# BridgeBoard.net
KiCad netlist of a schematic drawn in Altium Designer
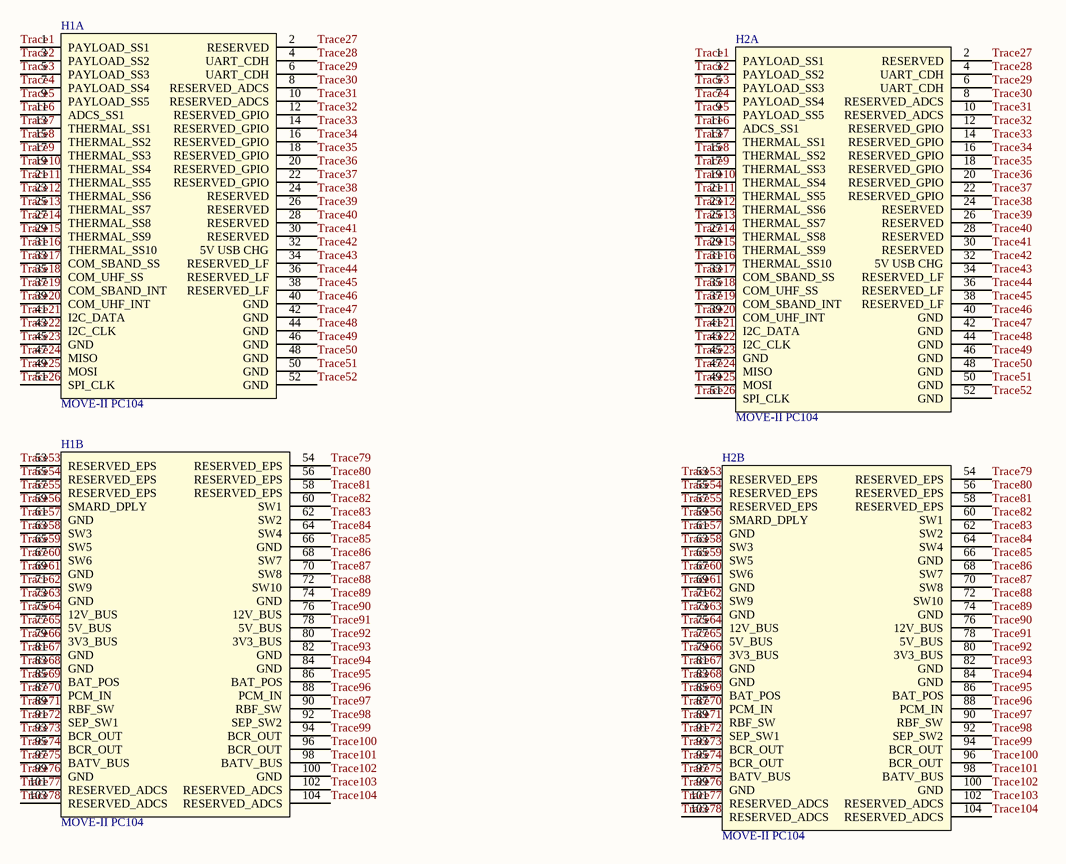
[diagram p0: BridgeBoard.SchDoc]

(export (version "E")
  (design (tool "Eeschema 10.0.6"))
  (components
    (comp (ref "H1")
      (value "MOVE-II PC104")
      (footprint "PC104")
      (libsource (lib "PC104_singleHeader") (part "MOVE-II PC104"))
    )
    (comp (ref "H2")
      (value "MOVE-II PC104")
      (footprint "PC104")
      (libsource (lib "PC104_singleHeader") (part "MOVE-II PC104"))
    )
  )
  (nets
    (net (code "1") (name "/Trace1") (class "Default")
      (node (ref "H1") (pin "1") (pinfunction "PAYLOAD_SS1_1") (pintype "passive"))
      (node (ref "H2") (pin "1") (pinfunction "PAYLOAD_SS1_1") (pintype "passive"))
    )
    (net (code "2") (name "/Trace2") (class "Default")
      (node (ref "H1") (pin "3") (pinfunction "PAYLOAD_SS2_3") (pintype "passive"))
      (node (ref "H2") (pin "3") (pinfunction "PAYLOAD_SS2_3") (pintype "passive"))
    )
    (net (code "3") (name "/Trace3") (class "Default")
      (node (ref "H1") (pin "5") (pinfunction "PAYLOAD_SS3_5") (pintype "passive"))
      (node (ref "H2") (pin "5") (pinfunction "PAYLOAD_SS3_5") (pintype "passive"))
    )
    (net (code "4") (name "/Trace4") (class "Default")
      (node (ref "H1") (pin "7") (pinfunction "PAYLOAD_SS4_7") (pintype "passive"))
      (node (ref "H2") (pin "7") (pinfunction "PAYLOAD_SS4_7") (pintype "passive"))
    )
    (net (code "5") (name "/Trace5") (class "Default")
      (node (ref "H1") (pin "9") (pinfunction "PAYLOAD_SS5_9") (pintype "passive"))
      (node (ref "H2") (pin "9") (pinfunction "PAYLOAD_SS5_9") (pintype "passive"))
    )
    (net (code "6") (name "/Trace6") (class "Default")
      (node (ref "H1") (pin "11") (pinfunction "ADCS_SS1_11") (pintype "passive"))
      (node (ref "H2") (pin "11") (pinfunction "ADCS_SS1_11") (pintype "passive"))
    )
    (net (code "7") (name "/Trace7") (class "Default")
      (node (ref "H1") (pin "13") (pinfunction "THERMAL_SS1_13") (pintype "passive"))
      (node (ref "H2") (pin "13") (pinfunction "THERMAL_SS1_13") (pintype "passive"))
    )
    (net (code "8") (name "/Trace8") (class "Default")
      (node (ref "H1") (pin "15") (pinfunction "THERMAL_SS2_15") (pintype "passive"))
      (node (ref "H2") (pin "15") (pinfunction "THERMAL_SS2_15") (pintype "passive"))
    )
    (net (code "9") (name "/Trace9") (class "Default")
      (node (ref "H1") (pin "17") (pinfunction "THERMAL_SS3_17") (pintype "passive"))
      (node (ref "H2") (pin "17") (pinfunction "THERMAL_SS3_17") (pintype "passive"))
    )
    (net (code "10") (name "/Trace10") (class "Default")
      (node (ref "H1") (pin "19") (pinfunction "THERMAL_SS4_19") (pintype "passive"))
      (node (ref "H2") (pin "19") (pinfunction "THERMAL_SS4_19") (pintype "passive"))
    )
    (net (code "11") (name "/Trace11") (class "Default")
      (node (ref "H1") (pin "21") (pinfunction "THERMAL_SS5_21") (pintype "passive"))
      (node (ref "H2") (pin "21") (pinfunction "THERMAL_SS5_21") (pintype "passive"))
    )
    (net (code "12") (name "/Trace12") (class "Default")
      (node (ref "H1") (pin "23") (pinfunction "THERMAL_SS6_23") (pintype "passive"))
      (node (ref "H2") (pin "23") (pinfunction "THERMAL_SS6_23") (pintype "passive"))
    )
    (net (code "13") (name "/Trace13") (class "Default")
      (node (ref "H1") (pin "25") (pinfunction "THERMAL_SS7_25") (pintype "passive"))
      (node (ref "H2") (pin "25") (pinfunction "THERMAL_SS7_25") (pintype "passive"))
    )
    (net (code "14") (name "/Trace14") (class "Default")
      (node (ref "H1") (pin "27") (pinfunction "THERMAL_SS8_27") (pintype "passive"))
      (node (ref "H2") (pin "27") (pinfunction "THERMAL_SS8_27") (pintype "passive"))
    )
    (net (code "15") (name "/Trace15") (class "Default")
      (node (ref "H1") (pin "29") (pinfunction "THERMAL_SS9_29") (pintype "passive"))
      (node (ref "H2") (pin "29") (pinfunction "THERMAL_SS9_29") (pintype "passive"))
    )
    (net (code "16") (name "/Trace16") (class "Default")
      (node (ref "H1") (pin "31") (pinfunction "THERMAL_SS10_31") (pintype "passive"))
      (node (ref "H2") (pin "31") (pinfunction "THERMAL_SS10_31") (pintype "passive"))
    )
    (net (code "17") (name "/Trace17") (class "Default")
      (node (ref "H1") (pin "33") (pinfunction "COM_SBAND_SS_33") (pintype "passive"))
      (node (ref "H2") (pin "33") (pinfunction "COM_SBAND_SS_33") (pintype "passive"))
    )
    (net (code "18") (name "/Trace18") (class "Default")
      (node (ref "H1") (pin "35") (pinfunction "COM_UHF_SS_35") (pintype "passive"))
      (node (ref "H2") (pin "35") (pinfunction "COM_UHF_SS_35") (pintype "passive"))
    )
    (net (code "19") (name "/Trace19") (class "Default")
      (node (ref "H1") (pin "37") (pinfunction "COM_SBAND_INT_37") (pintype "passive"))
      (node (ref "H2") (pin "37") (pinfunction "COM_SBAND_INT_37") (pintype "passive"))
    )
    (net (code "20") (name "/Trace20") (class "Default")
      (node (ref "H1") (pin "39") (pinfunction "COM_UHF_INT_39") (pintype "passive"))
      (node (ref "H2") (pin "39") (pinfunction "COM_UHF_INT_39") (pintype "passive"))
    )
    (net (code "21") (name "/Trace21") (class "Default")
      (node (ref "H1") (pin "41") (pinfunction "I2C_DATA_41") (pintype "passive"))
      (node (ref "H2") (pin "41") (pinfunction "I2C_DATA_41") (pintype "passive"))
    )
    (net (code "22") (name "/Trace22") (class "Default")
      (node (ref "H1") (pin "43") (pinfunction "I2C_CLK_43") (pintype "passive"))
      (node (ref "H2") (pin "43") (pinfunction "I2C_CLK_43") (pintype "passive"))
    )
    (net (code "23") (name "/Trace23") (class "Default")
      (node (ref "H1") (pin "45") (pinfunction "GND_45") (pintype "passive"))
      (node (ref "H2") (pin "45") (pinfunction "GND_45") (pintype "passive"))
    )
    (net (code "24") (name "/Trace24") (class "Default")
      (node (ref "H1") (pin "47") (pinfunction "MISO_47") (pintype "passive"))
      (node (ref "H2") (pin "47") (pinfunction "MISO_47") (pintype "passive"))
    )
    (net (code "25") (name "/Trace25") (class "Default")
      (node (ref "H1") (pin "49") (pinfunction "MOSI_49") (pintype "passive"))
      (node (ref "H2") (pin "49") (pinfunction "MOSI_49") (pintype "passive"))
    )
    (net (code "26") (name "/Trace26") (class "Default")
      (node (ref "H1") (pin "51") (pinfunction "SPI_CLK_51") (pintype "passive"))
      (node (ref "H2") (pin "51") (pinfunction "SPI_CLK_51") (pintype "passive"))
    )
    (net (code "27") (name "/Trace27") (class "Default")
      (node (ref "H1") (pin "2") (pinfunction "RESERVED_2") (pintype "passive"))
      (node (ref "H2") (pin "2") (pinfunction "RESERVED_2") (pintype "passive"))
    )
    (net (code "28") (name "/Trace28") (class "Default")
      (node (ref "H1") (pin "4") (pinfunction "UART_CDH_4") (pintype "passive"))
      (node (ref "H2") (pin "4") (pinfunction "UART_CDH_4") (pintype "passive"))
    )
    (net (code "29") (name "/Trace29") (class "Default")
      (node (ref "H1") (pin "6") (pinfunction "UART_CDH_6") (pintype "passive"))
      (node (ref "H2") (pin "6") (pinfunction "UART_CDH_6") (pintype "passive"))
    )
    (net (code "30") (name "/Trace30") (class "Default")
      (node (ref "H1") (pin "8") (pinfunction "RESERVED_ADCS_8") (pintype "passive"))
      (node (ref "H2") (pin "8") (pinfunction "RESERVED_ADCS_8") (pintype "passive"))
    )
    (net (code "31") (name "/Trace31") (class "Default")
      (node (ref "H1") (pin "10") (pinfunction "RESERVED_ADCS_10") (pintype "passive"))
      (node (ref "H2") (pin "10") (pinfunction "RESERVED_ADCS_10") (pintype "passive"))
    )
    (net (code "32") (name "/Trace32") (class "Default")
      (node (ref "H1") (pin "12") (pinfunction "RESERVED_GPIO_12") (pintype "passive"))
      (node (ref "H2") (pin "12") (pinfunction "RESERVED_GPIO_12") (pintype "passive"))
    )
    (net (code "33") (name "/Trace33") (class "Default")
      (node (ref "H1") (pin "14") (pinfunction "RESERVED_GPIO_14") (pintype "passive"))
      (node (ref "H2") (pin "14") (pinfunction "RESERVED_GPIO_14") (pintype "passive"))
    )
    (net (code "34") (name "/Trace34") (class "Default")
      (node (ref "H1") (pin "16") (pinfunction "RESERVED_GPIO_16") (pintype "passive"))
      (node (ref "H2") (pin "16") (pinfunction "RESERVED_GPIO_16") (pintype "passive"))
    )
    (net (code "35") (name "/Trace35") (class "Default")
      (node (ref "H1") (pin "18") (pinfunction "RESERVED_GPIO_18") (pintype "passive"))
      (node (ref "H2") (pin "18") (pinfunction "RESERVED_GPIO_18") (pintype "passive"))
    )
    (net (code "36") (name "/Trace36") (class "Default")
      (node (ref "H1") (pin "20") (pinfunction "RESERVED_GPIO_20") (pintype "passive"))
      (node (ref "H2") (pin "20") (pinfunction "RESERVED_GPIO_20") (pintype "passive"))
    )
    (net (code "37") (name "/Trace37") (class "Default")
      (node (ref "H1") (pin "22") (pinfunction "RESERVED_GPIO_22") (pintype "passive"))
      (node (ref "H2") (pin "22") (pinfunction "RESERVED_GPIO_22") (pintype "passive"))
    )
    (net (code "38") (name "/Trace38") (class "Default")
      (node (ref "H1") (pin "24") (pinfunction "RESERVED_24") (pintype "passive"))
      (node (ref "H2") (pin "24") (pinfunction "RESERVED_24") (pintype "passive"))
    )
    (net (code "39") (name "/Trace39") (class "Default")
      (node (ref "H1") (pin "26") (pinfunction "RESERVED_26") (pintype "passive"))
      (node (ref "H2") (pin "26") (pinfunction "RESERVED_26") (pintype "passive"))
    )
    (net (code "40") (name "/Trace40") (class "Default")
      (node (ref "H1") (pin "28") (pinfunction "RESERVED_28") (pintype "passive"))
      (node (ref "H2") (pin "28") (pinfunction "RESERVED_28") (pintype "passive"))
    )
    (net (code "41") (name "/Trace41") (class "Default")
      (node (ref "H1") (pin "30") (pinfunction "RESERVED_30") (pintype "passive"))
      (node (ref "H2") (pin "30") (pinfunction "RESERVED_30") (pintype "passive"))
    )
    (net (code "42") (name "/Trace42") (class "Default")
      (node (ref "H1") (pin "32") (pinfunction "5V_USB_CHG_32") (pintype "passive"))
      (node (ref "H2") (pin "32") (pinfunction "5V_USB_CHG_32") (pintype "passive"))
    )
    (net (code "43") (name "/Trace43") (class "Default")
      (node (ref "H1") (pin "34") (pinfunction "RESERVED_LF_34") (pintype "passive"))
      (node (ref "H2") (pin "34") (pinfunction "RESERVED_LF_34") (pintype "passive"))
    )
    (net (code "44") (name "/Trace44") (class "Default")
      (node (ref "H1") (pin "36") (pinfunction "RESERVED_LF_36") (pintype "passive"))
      (node (ref "H2") (pin "36") (pinfunction "RESERVED_LF_36") (pintype "passive"))
    )
    (net (code "45") (name "/Trace45") (class "Default")
      (node (ref "H1") (pin "38") (pinfunction "RESERVED_LF_38") (pintype "passive"))
      (node (ref "H2") (pin "38") (pinfunction "RESERVED_LF_38") (pintype "passive"))
    )
    (net (code "46") (name "/Trace46") (class "Default")
      (node (ref "H1") (pin "40") (pinfunction "GND_40") (pintype "passive"))
      (node (ref "H2") (pin "40") (pinfunction "GND_40") (pintype "passive"))
    )
    (net (code "47") (name "/Trace47") (class "Default")
      (node (ref "H1") (pin "42") (pinfunction "GND_42") (pintype "passive"))
      (node (ref "H2") (pin "42") (pinfunction "GND_42") (pintype "passive"))
    )
    (net (code "48") (name "/Trace48") (class "Default")
      (node (ref "H1") (pin "44") (pinfunction "GND_44") (pintype "passive"))
      (node (ref "H2") (pin "44") (pinfunction "GND_44") (pintype "passive"))
    )
    (net (code "49") (name "/Trace49") (class "Default")
      (node (ref "H1") (pin "46") (pinfunction "GND_46") (pintype "passive"))
      (node (ref "H2") (pin "46") (pinfunction "GND_46") (pintype "passive"))
    )
    (net (code "50") (name "/Trace50") (class "Default")
      (node (ref "H1") (pin "48") (pinfunction "GND_48") (pintype "passive"))
      (node (ref "H2") (pin "48") (pinfunction "GND_48") (pintype "passive"))
    )
    (net (code "51") (name "/Trace51") (class "Default")
      (node (ref "H1") (pin "50") (pinfunction "GND_50") (pintype "passive"))
      (node (ref "H2") (pin "50") (pinfunction "GND_50") (pintype "passive"))
    )
    (net (code "52") (name "/Trace52") (class "Default")
      (node (ref "H1") (pin "52") (pinfunction "GND_52") (pintype "passive"))
      (node (ref "H2") (pin "52") (pinfunction "GND_52") (pintype "passive"))
    )
    (net (code "53") (name "/Trace53") (class "Default")
      (node (ref "H1") (pin "53") (pinfunction "RESERVED_EPS_53") (pintype "passive"))
      (node (ref "H2") (pin "53") (pinfunction "RESERVED_EPS_53") (pintype "passive"))
    )
    (net (code "54") (name "/Trace54") (class "Default")
      (node (ref "H1") (pin "55") (pinfunction "RESERVED_EPS_55") (pintype "passive"))
      (node (ref "H2") (pin "55") (pinfunction "RESERVED_EPS_55") (pintype "passive"))
    )
    (net (code "55") (name "/Trace55") (class "Default")
      (node (ref "H1") (pin "57") (pinfunction "RESERVED_EPS_57") (pintype "passive"))
      (node (ref "H2") (pin "57") (pinfunction "RESERVED_EPS_57") (pintype "passive"))
    )
    (net (code "56") (name "/Trace56") (class "Default")
      (node (ref "H1") (pin "59") (pinfunction "SMARD_DPLY_59") (pintype "passive"))
      (node (ref "H2") (pin "59") (pinfunction "SMARD_DPLY_59") (pintype "passive"))
    )
    (net (code "57") (name "/Trace57") (class "Default")
      (node (ref "H1") (pin "61") (pinfunction "GND_61") (pintype "passive"))
      (node (ref "H2") (pin "61") (pinfunction "GND_61") (pintype "passive"))
    )
    (net (code "58") (name "/Trace58") (class "Default")
      (node (ref "H1") (pin "63") (pinfunction "SW3_63") (pintype "passive"))
      (node (ref "H2") (pin "63") (pinfunction "SW3_63") (pintype "passive"))
    )
    (net (code "59") (name "/Trace59") (class "Default")
      (node (ref "H1") (pin "65") (pinfunction "SW5_65") (pintype "passive"))
      (node (ref "H2") (pin "65") (pinfunction "SW5_65") (pintype "passive"))
    )
    (net (code "60") (name "/Trace60") (class "Default")
      (node (ref "H1") (pin "67") (pinfunction "SW6_67") (pintype "passive"))
      (node (ref "H2") (pin "67") (pinfunction "SW6_67") (pintype "passive"))
    )
    (net (code "61") (name "/Trace61") (class "Default")
      (node (ref "H1") (pin "69") (pinfunction "GND_69") (pintype "passive"))
      (node (ref "H2") (pin "69") (pinfunction "GND_69") (pintype "passive"))
    )
    (net (code "62") (name "/Trace62") (class "Default")
      (node (ref "H1") (pin "71") (pinfunction "SW9_71") (pintype "passive"))
      (node (ref "H2") (pin "71") (pinfunction "SW9_71") (pintype "passive"))
    )
    (net (code "63") (name "/Trace63") (class "Default")
      (node (ref "H1") (pin "73") (pinfunction "GND_73") (pintype "passive"))
      (node (ref "H2") (pin "73") (pinfunction "GND_73") (pintype "passive"))
    )
    (net (code "64") (name "/Trace64") (class "Default")
      (node (ref "H1") (pin "75") (pinfunction "12V_BUS_75") (pintype "passive"))
      (node (ref "H2") (pin "75") (pinfunction "12V_BUS_75") (pintype "passive"))
    )
    (net (code "65") (name "/Trace65") (class "Default")
      (node (ref "H1") (pin "77") (pinfunction "5V_BUS_77") (pintype "passive"))
      (node (ref "H2") (pin "77") (pinfunction "5V_BUS_77") (pintype "passive"))
    )
    (net (code "66") (name "/Trace66") (class "Default")
      (node (ref "H1") (pin "79") (pinfunction "3V3_BUS_79") (pintype "passive"))
      (node (ref "H2") (pin "79") (pinfunction "3V3_BUS_79") (pintype "passive"))
    )
    (net (code "67") (name "/Trace67") (class "Default")
      (node (ref "H1") (pin "81") (pinfunction "GND_81") (pintype "passive"))
      (node (ref "H2") (pin "81") (pinfunction "GND_81") (pintype "passive"))
    )
    (net (code "68") (name "/Trace68") (class "Default")
      (node (ref "H1") (pin "83") (pinfunction "GND_83") (pintype "passive"))
      (node (ref "H2") (pin "83") (pinfunction "GND_83") (pintype "passive"))
    )
    (net (code "69") (name "/Trace69") (class "Default")
      (node (ref "H1") (pin "85") (pinfunction "BAT_POS_85") (pintype "passive"))
      (node (ref "H2") (pin "85") (pinfunction "BAT_POS_85") (pintype "passive"))
    )
    (net (code "70") (name "/Trace70") (class "Default")
      (node (ref "H1") (pin "87") (pinfunction "PCM_IN_87") (pintype "passive"))
      (node (ref "H2") (pin "87") (pinfunction "PCM_IN_87") (pintype "passive"))
    )
    (net (code "71") (name "/Trace71") (class "Default")
      (node (ref "H1") (pin "89") (pinfunction "RBF_SW_89") (pintype "passive"))
      (node (ref "H2") (pin "89") (pinfunction "RBF_SW_89") (pintype "passive"))
    )
    (net (code "72") (name "/Trace72") (class "Default")
      (node (ref "H1") (pin "91") (pinfunction "SEP_SW1_91") (pintype "passive"))
      (node (ref "H2") (pin "91") (pinfunction "SEP_SW1_91") (pintype "passive"))
    )
    (net (code "73") (name "/Trace73") (class "Default")
      (node (ref "H1") (pin "93") (pinfunction "BCR_OUT_93") (pintype "passive"))
      (node (ref "H2") (pin "93") (pinfunction "BCR_OUT_93") (pintype "passive"))
    )
    (net (code "74") (name "/Trace74") (class "Default")
      (node (ref "H1") (pin "95") (pinfunction "BCR_OUT_95") (pintype "passive"))
      (node (ref "H2") (pin "95") (pinfunction "BCR_OUT_95") (pintype "passive"))
    )
    (net (code "75") (name "/Trace75") (class "Default")
      (node (ref "H1") (pin "97") (pinfunction "BATV_BUS_97") (pintype "passive"))
      (node (ref "H2") (pin "97") (pinfunction "BATV_BUS_97") (pintype "passive"))
    )
    (net (code "76") (name "/Trace76") (class "Default")
      (node (ref "H1") (pin "99") (pinfunction "GND_99") (pintype "passive"))
      (node (ref "H2") (pin "99") (pinfunction "GND_99") (pintype "passive"))
    )
    (net (code "77") (name "/Trace77") (class "Default")
      (node (ref "H1") (pin "101") (pinfunction "RESERVED_ADCS_101") (pintype "passive"))
      (node (ref "H2") (pin "101") (pinfunction "RESERVED_ADCS_101") (pintype "passive"))
    )
    (net (code "78") (name "/Trace78") (class "Default")
      (node (ref "H1") (pin "103") (pinfunction "RESERVED_ADCS_103") (pintype "passive"))
      (node (ref "H2") (pin "103") (pinfunction "RESERVED_ADCS_103") (pintype "passive"))
    )
    (net (code "79") (name "/Trace79") (class "Default")
      (node (ref "H1") (pin "54") (pinfunction "RESERVED_EPS_54") (pintype "passive"))
      (node (ref "H2") (pin "54") (pinfunction "RESERVED_EPS_54") (pintype "passive"))
    )
    (net (code "80") (name "/Trace80") (class "Default")
      (node (ref "H1") (pin "56") (pinfunction "RESERVED_EPS_56") (pintype "passive"))
      (node (ref "H2") (pin "56") (pinfunction "RESERVED_EPS_56") (pintype "passive"))
    )
    (net (code "81") (name "/Trace81") (class "Default")
      (node (ref "H1") (pin "58") (pinfunction "RESERVED_EPS_58") (pintype "passive"))
      (node (ref "H2") (pin "58") (pinfunction "RESERVED_EPS_58") (pintype "passive"))
    )
    (net (code "82") (name "/Trace82") (class "Default")
      (node (ref "H1") (pin "60") (pinfunction "SW1_60") (pintype "passive"))
      (node (ref "H2") (pin "60") (pinfunction "SW1_60") (pintype "passive"))
    )
    (net (code "83") (name "/Trace83") (class "Default")
      (node (ref "H1") (pin "62") (pinfunction "SW2_62") (pintype "passive"))
      (node (ref "H2") (pin "62") (pinfunction "SW2_62") (pintype "passive"))
    )
    (net (code "84") (name "/Trace84") (class "Default")
      (node (ref "H1") (pin "64") (pinfunction "SW4_64") (pintype "passive"))
      (node (ref "H2") (pin "64") (pinfunction "SW4_64") (pintype "passive"))
    )
    (net (code "85") (name "/Trace85") (class "Default")
      (node (ref "H1") (pin "66") (pinfunction "GND_66") (pintype "passive"))
      (node (ref "H2") (pin "66") (pinfunction "GND_66") (pintype "passive"))
    )
    (net (code "86") (name "/Trace86") (class "Default")
      (node (ref "H1") (pin "68") (pinfunction "SW7_68") (pintype "passive"))
      (node (ref "H2") (pin "68") (pinfunction "SW7_68") (pintype "passive"))
    )
    (net (code "87") (name "/Trace87") (class "Default")
      (node (ref "H1") (pin "70") (pinfunction "SW8_70") (pintype "passive"))
      (node (ref "H2") (pin "70") (pinfunction "SW8_70") (pintype "passive"))
    )
    (net (code "88") (name "/Trace88") (class "Default")
      (node (ref "H1") (pin "72") (pinfunction "SW10_72") (pintype "passive"))
      (node (ref "H2") (pin "72") (pinfunction "SW10_72") (pintype "passive"))
    )
    (net (code "89") (name "/Trace89") (class "Default")
      (node (ref "H1") (pin "74") (pinfunction "GND_74") (pintype "passive"))
      (node (ref "H2") (pin "74") (pinfunction "GND_74") (pintype "passive"))
    )
    (net (code "90") (name "/Trace90") (class "Default")
      (node (ref "H1") (pin "76") (pinfunction "12V_BUS_76") (pintype "passive"))
      (node (ref "H2") (pin "76") (pinfunction "12V_BUS_76") (pintype "passive"))
    )
    (net (code "91") (name "/Trace91") (class "Default")
      (node (ref "H1") (pin "78") (pinfunction "5V_BUS_78") (pintype "passive"))
      (node (ref "H2") (pin "78") (pinfunction "5V_BUS_78") (pintype "passive"))
    )
    (net (code "92") (name "/Trace92") (class "Default")
      (node (ref "H1") (pin "80") (pinfunction "3V3_BUS_80") (pintype "passive"))
      (node (ref "H2") (pin "80") (pinfunction "3V3_BUS_80") (pintype "passive"))
    )
    (net (code "93") (name "/Trace93") (class "Default")
      (node (ref "H1") (pin "82") (pinfunction "GND_82") (pintype "passive"))
      (node (ref "H2") (pin "82") (pinfunction "GND_82") (pintype "passive"))
    )
    (net (code "94") (name "/Trace94") (class "Default")
      (node (ref "H1") (pin "84") (pinfunction "GND_84") (pintype "passive"))
      (node (ref "H2") (pin "84") (pinfunction "GND_84") (pintype "passive"))
    )
    (net (code "95") (name "/Trace95") (class "Default")
      (node (ref "H1") (pin "86") (pinfunction "BAT_POS_86") (pintype "passive"))
      (node (ref "H2") (pin "86") (pinfunction "BAT_POS_86") (pintype "passive"))
    )
    (net (code "96") (name "/Trace96") (class "Default")
      (node (ref "H1") (pin "88") (pinfunction "PCM_IN_88") (pintype "passive"))
      (node (ref "H2") (pin "88") (pinfunction "PCM_IN_88") (pintype "passive"))
    )
    (net (code "97") (name "/Trace97") (class "Default")
      (node (ref "H1") (pin "90") (pinfunction "RBF_SW_90") (pintype "passive"))
      (node (ref "H2") (pin "90") (pinfunction "RBF_SW_90") (pintype "passive"))
    )
    (net (code "98") (name "/Trace98") (class "Default")
      (node (ref "H1") (pin "92") (pinfunction "SEP_SW2_92") (pintype "passive"))
      (node (ref "H2") (pin "92") (pinfunction "SEP_SW2_92") (pintype "passive"))
    )
    (net (code "99") (name "/Trace99") (class "Default")
      (node (ref "H1") (pin "94") (pinfunction "BCR_OUT_94") (pintype "passive"))
      (node (ref "H2") (pin "94") (pinfunction "BCR_OUT_94") (pintype "passive"))
    )
    (net (code "100") (name "/Trace100") (class "Default")
      (node (ref "H1") (pin "96") (pinfunction "BCR_OUT_96") (pintype "passive"))
      (node (ref "H2") (pin "96") (pinfunction "BCR_OUT_96") (pintype "passive"))
    )
    (net (code "101") (name "/Trace101") (class "Default")
      (node (ref "H1") (pin "98") (pinfunction "BATV_BUS_98") (pintype "passive"))
      (node (ref "H2") (pin "98") (pinfunction "BATV_BUS_98") (pintype "passive"))
    )
    (net (code "102") (name "/Trace102") (class "Default")
      (node (ref "H1") (pin "100") (pinfunction "GND_100") (pintype "passive"))
      (node (ref "H2") (pin "100") (pinfunction "GND_100") (pintype "passive"))
    )
    (net (code "103") (name "/Trace103") (class "Default")
      (node (ref "H1") (pin "102") (pinfunction "RESERVED_ADCS_102") (pintype "passive"))
      (node (ref "H2") (pin "102") (pinfunction "RESERVED_ADCS_102") (pintype "passive"))
    )
    (net (code "104") (name "/Trace104") (class "Default")
      (node (ref "H1") (pin "104") (pinfunction "RESERVED_ADCS_104") (pintype "passive"))
      (node (ref "H2") (pin "104") (pinfunction "RESERVED_ADCS_104") (pintype "passive"))
    )
  )
)
